# Sheet1.net
KiCad netlist of a schematic drawn in Altium Designer
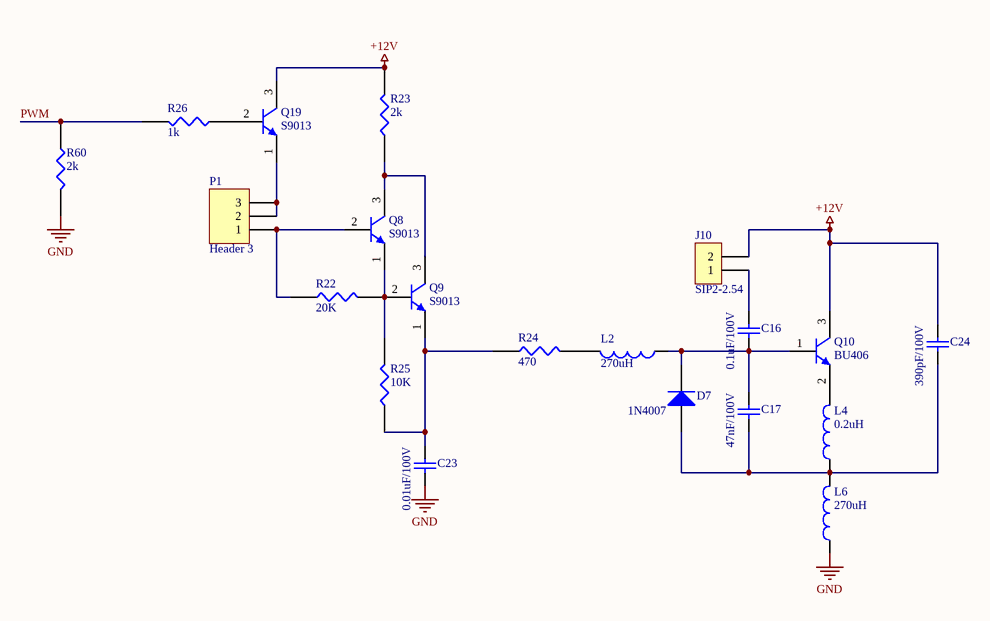
[diagram p0: Sheet1.SchDoc]

(export (version "E")
  (design (tool "Eeschema 10.0.6"))
  (components
    (comp (ref "C16")
      (value "0.1uF/100V")
      (footprint "CAP_5MM")
      (description "Capacitor")
      (fields (field (name "PUBLISHER") "Altium Limited"))
      (libsource (lib "Miscellaneous Devices") (part "Cap"))
    )
    (comp (ref "C17")
      (value "47nF/100V")
      (footprint "CAP_5MM")
      (description "Capacitor")
      (fields (field (name "PUBLISHER") "Altium Limited"))
      (libsource (lib "Miscellaneous Devices") (part "Cap"))
    )
    (comp (ref "C23")
      (value "0.01uF/100V")
      (footprint "0603c")
      (description "Capacitor")
      (fields (field (name "PUBLISHER") "Altium Limited"))
      (libsource (lib "Miscellaneous Devices") (part "Cap"))
    )
    (comp (ref "C24")
      (value "390pF/100V")
      (footprint "CAP_5MM")
      (description "Capacitor")
      (fields (field (name "PUBLISHER") "Altium Limited"))
      (libsource (lib "Miscellaneous Devices") (part "Cap"))
    )
    (comp (ref "D7")
      (value "1N4007")
      (footprint "DIO10.46-5.3x2.8")
      (description "Default Diode")
      (fields (field (name "PUBLISHER") "Altium Limited"))
      (libsource (lib "SM") (part "Diode_2"))
    )
    (comp (ref "J10")
      (value "SIP2-2.54")
      (footprint "SIP-2L")
      (description "CN-SIP2-2.54")
      (libsource (lib "接插件") (part "SIP2-2.54"))
    )
    (comp (ref "L2")
      (value "270uH")
      (footprint "6*8")
      (description "Inductor")
      (fields (field (name "PUBLISHER") "Altium Limited"))
      (libsource (lib "Miscellaneous Devices") (part "Inductor"))
    )
    (comp (ref "L4")
      (value "0.2uH")
      (footprint "6*8")
      (description "Inductor")
      (fields (field (name "PUBLISHER") "Altium Limited"))
      (libsource (lib "Miscellaneous Devices") (part "Inductor"))
    )
    (comp (ref "L6")
      (value "270uH")
      (footprint "6*8")
      (description "Inductor")
      (fields (field (name "PUBLISHER") "Altium Limited"))
      (libsource (lib "Miscellaneous Devices") (part "Inductor"))
    )
    (comp (ref "P1")
      (value "Header 3")
      (footprint "HDR1X3")
      (description "Header, 3-Pin")
      (fields (field (name "PUBLISHER") "Altium Limited"))
      (libsource (lib "Miscellaneous Connectors") (part "Header 3"))
    )
    (comp (ref "Q8")
      (value "S9013")
      (footprint "to-92")
      (description "NPN Bipolar Transistor")
      (fields (field (name "PUBLISHER") "Altium Limited"))
      (libsource (lib "Miscellaneous Devices") (part "NPN"))
    )
    (comp (ref "Q9")
      (value "S9013")
      (footprint "to-92")
      (description "NPN Bipolar Transistor")
      (fields (field (name "PUBLISHER") "Altium Limited"))
      (libsource (lib "Miscellaneous Devices") (part "NPN"))
    )
    (comp (ref "Q10")
      (value "BU406")
      (footprint "to220")
      (description "NPN Bipolar Transistor")
      (fields (field (name "PUBLISHER") "Altium Limited"))
      (libsource (lib "") (part "NPN_1"))
    )
    (comp (ref "Q19")
      (value "S9013")
      (footprint "to-92")
      (description "NPN Bipolar Transistor")
      (fields (field (name "PUBLISHER") "Altium Limited"))
      (libsource (lib "Miscellaneous Devices") (part "NPN"))
    )
    (comp (ref "R22") (value "20K") (footprint "0603r") (libsource (lib "其他电阻") (part "RES1")))
    (comp (ref "R23") (value "2k") (footprint "0603R") (libsource (lib "其他电阻") (part "RES1")))
    (comp (ref "R24") (value "470") (footprint "0805R") (libsource (lib "其他电阻") (part "RES1")))
    (comp (ref "R25") (value "10K") (footprint "0603R") (libsource (lib "其他电阻") (part "RES1")))
    (comp (ref "R26") (value "1k") (footprint "0603R") (libsource (lib "其他电阻") (part "RES1")))
    (comp (ref "R60") (value "2k") (footprint "0603R") (libsource (lib "其他电阻") (part "RES1")))
  )
  (nets
    (net (code "1") (name "+12V") (class "Default")
      (node (ref "C24") (pin "2") (pinfunction "2_2") (pintype "passive"))
      (node (ref "J10") (pin "2") (pinfunction "2_2") (pintype "passive"))
      (node (ref "Q10") (pin "3") (pinfunction "C_3") (pintype "passive"))
      (node (ref "Q19") (pin "3") (pinfunction "C_3") (pintype "passive"))
      (node (ref "R23") (pin "2") (pinfunction "2_2") (pintype "passive"))
    )
    (net (code "2") (name "/PWM") (class "Default")
      (node (ref "R26") (pin "2") (pinfunction "2_2") (pintype "passive"))
      (node (ref "R60") (pin "1") (pinfunction "1_1") (pintype "passive"))
    )
    (net (code "3") (name "GND") (class "Default")
      (node (ref "C23") (pin "1") (pinfunction "1_1") (pintype "passive"))
      (node (ref "L6") (pin "1") (pinfunction "1_1") (pintype "passive"))
      (node (ref "R60") (pin "2") (pinfunction "2_2") (pintype "passive"))
    )
    (net (code "4") (name "Net-(C16-Pad2)") (class "Default")
      (node (ref "C16") (pin "2") (pinfunction "2_2") (pintype "passive"))
      (node (ref "J10") (pin "1") (pinfunction "1_1") (pintype "passive"))
    )
    (net (code "5") (name "Net-(D7-A)") (class "Default")
      (node (ref "C17") (pin "1") (pinfunction "1_1") (pintype "passive"))
      (node (ref "C24") (pin "1") (pinfunction "1_1") (pintype "passive"))
      (node (ref "D7") (pin "1") (pinfunction "A_1") (pintype "passive"))
      (node (ref "L4") (pin "1") (pinfunction "1_1") (pintype "passive"))
      (node (ref "L6") (pin "2") (pinfunction "2_2") (pintype "passive"))
    )
    (net (code "6") (name "Net-(D7-K)") (class "Default")
      (node (ref "C16") (pin "1") (pinfunction "1_1") (pintype "passive"))
      (node (ref "C17") (pin "2") (pinfunction "2_2") (pintype "passive"))
      (node (ref "D7") (pin "2") (pinfunction "K_2") (pintype "passive"))
      (node (ref "L2") (pin "1") (pinfunction "1_1") (pintype "passive"))
      (node (ref "Q10") (pin "1") (pinfunction "B_1") (pintype "passive"))
    )
    (net (code "7") (name "Net-(L2-Pad2)") (class "Default")
      (node (ref "L2") (pin "2") (pinfunction "2_2") (pintype "passive"))
      (node (ref "R24") (pin "2") (pinfunction "2_2") (pintype "passive"))
    )
    (net (code "8") (name "Net-(Q8-B)") (class "Default")
      (node (ref "P1") (pin "1") (pinfunction "1_1") (pintype "passive"))
      (node (ref "Q8") (pin "2") (pinfunction "B_2") (pintype "passive"))
      (node (ref "R22") (pin "1") (pinfunction "1_1") (pintype "passive"))
    )
    (net (code "9") (name "Net-(Q8-C)") (class "Default")
      (node (ref "Q8") (pin "3") (pinfunction "C_3") (pintype "passive"))
      (node (ref "Q9") (pin "3") (pinfunction "C_3") (pintype "passive"))
      (node (ref "R23") (pin "1") (pinfunction "1_1") (pintype "passive"))
    )
    (net (code "10") (name "Net-(Q8-E)") (class "Default")
      (node (ref "Q8") (pin "1") (pinfunction "E_1") (pintype "passive"))
      (node (ref "Q9") (pin "2") (pinfunction "B_2") (pintype "passive"))
      (node (ref "R22") (pin "2") (pinfunction "2_2") (pintype "passive"))
      (node (ref "R25") (pin "2") (pinfunction "2_2") (pintype "passive"))
    )
    (net (code "11") (name "Net-(Q9-E)") (class "Default")
      (node (ref "C23") (pin "2") (pinfunction "2_2") (pintype "passive"))
      (node (ref "Q9") (pin "1") (pinfunction "E_1") (pintype "passive"))
      (node (ref "R24") (pin "1") (pinfunction "1_1") (pintype "passive"))
      (node (ref "R25") (pin "1") (pinfunction "1_1") (pintype "passive"))
    )
    (net (code "12") (name "Net-(Q10-E)") (class "Default")
      (node (ref "L4") (pin "2") (pinfunction "2_2") (pintype "passive"))
      (node (ref "Q10") (pin "2") (pinfunction "E_2") (pintype "passive"))
    )
    (net (code "13") (name "Net-(Q19-B)") (class "Default")
      (node (ref "Q19") (pin "2") (pinfunction "B_2") (pintype "passive"))
      (node (ref "R26") (pin "1") (pinfunction "1_1") (pintype "passive"))
    )
    (net (code "14") (name "Net-(Q19-E)") (class "Default")
      (node (ref "P1") (pin "2") (pinfunction "2_2") (pintype "passive"))
      (node (ref "P1") (pin "3") (pinfunction "3_3") (pintype "passive"))
      (node (ref "Q19") (pin "1") (pinfunction "E_1") (pintype "passive"))
    )
  )
)
